# HbridgeDesignBlock.net
KiCad netlist of a schematic drawn in EAGLE
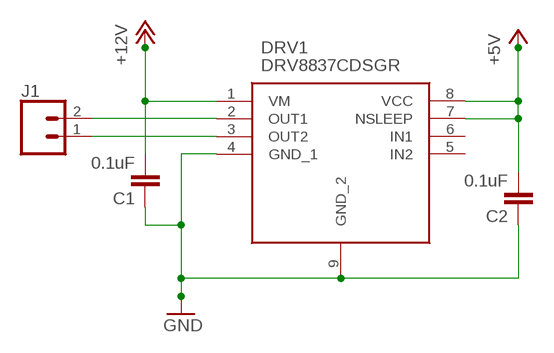
[diagram p0: schematic, sheet 1]

(export (version "E")
  (design (tool "Eeschema 10.0.6"))
  (components
    (comp (ref "C1")
      (value "0.1uF")
      (footprint "eagle-import:0603")
      (libsource (lib "eagle-import") (part "0.1UF-0603-25V-(+80/-20%)"))
    )
    (comp (ref "C2")
      (value "0.1uF")
      (footprint "eagle-import:0603")
      (libsource (lib "eagle-import") (part "0.1UF-0603-25V-(+80/-20%)"))
    )
    (comp (ref "DRV1")
      (value "DRV8837CDSGR")
      (footprint "eagle-import:SON50P200X200X80-9N")
      (fields (field (name "MOUSER_PART_NUMBER") "595-DRV8837CDSGR"))
      (libsource (lib "eagle-import") (part "DRV8837CDSGR"))
    )
    (comp (ref "J1")
      (value "CONN_02")
      (footprint "eagle-import:1X02")
      (libsource (lib "eagle-import") (part "CONN_02"))
    )
  )
  (nets
    (net (code "1") (name "+5V") (class "Default")
      (node (ref "C2") (pin "2") (pinfunction "2_2") (pintype "passive"))
      (node (ref "DRV1") (pin "7") (pinfunction "NSLEEP_7") (pintype "bidirectional"))
      (node (ref "DRV1") (pin "8") (pinfunction "VCC_8") (pintype "bidirectional"))
    )
    (net (code "2") (name "+12V") (class "Default")
      (node (ref "C1") (pin "2") (pinfunction "2_2") (pintype "passive"))
      (node (ref "DRV1") (pin "1") (pinfunction "VM_1") (pintype "bidirectional"))
    )
    (net (code "3") (name "GND") (class "Default")
      (node (ref "C1") (pin "1") (pinfunction "1_1") (pintype "passive"))
      (node (ref "C2") (pin "1") (pinfunction "1_1") (pintype "passive"))
      (node (ref "DRV1") (pin "4") (pinfunction "GND_1_4") (pintype "bidirectional"))
      (node (ref "DRV1") (pin "9") (pinfunction "GND_2_9") (pintype "bidirectional"))
    )
    (net (code "4") (name "Net-(DRV1-OUT1)") (class "Default")
      (node (ref "DRV1") (pin "2") (pinfunction "OUT1_2") (pintype "bidirectional"))
      (node (ref "J1") (pin "2") (pinfunction "2_2") (pintype "passive"))
    )
    (net (code "5") (name "Net-(DRV1-OUT2)") (class "Default")
      (node (ref "DRV1") (pin "3") (pinfunction "OUT2_3") (pintype "bidirectional"))
      (node (ref "J1") (pin "1") (pinfunction "1_1") (pintype "passive"))
    )
    (net (code "6") (name "unconnected-(DRV1-IN1-Pad6)") (class "Default")
      (node (ref "DRV1") (pin "6") (pinfunction "IN1_6") (pintype "bidirectional"))
    )
    (net (code "7") (name "unconnected-(DRV1-IN2-Pad5)") (class "Default")
      (node (ref "DRV1") (pin "5") (pinfunction "IN2_5") (pintype "bidirectional"))
    )
  )
)
